# ATmega328P-StripBd.net
KiCad netlist of a schematic drawn in EAGLE
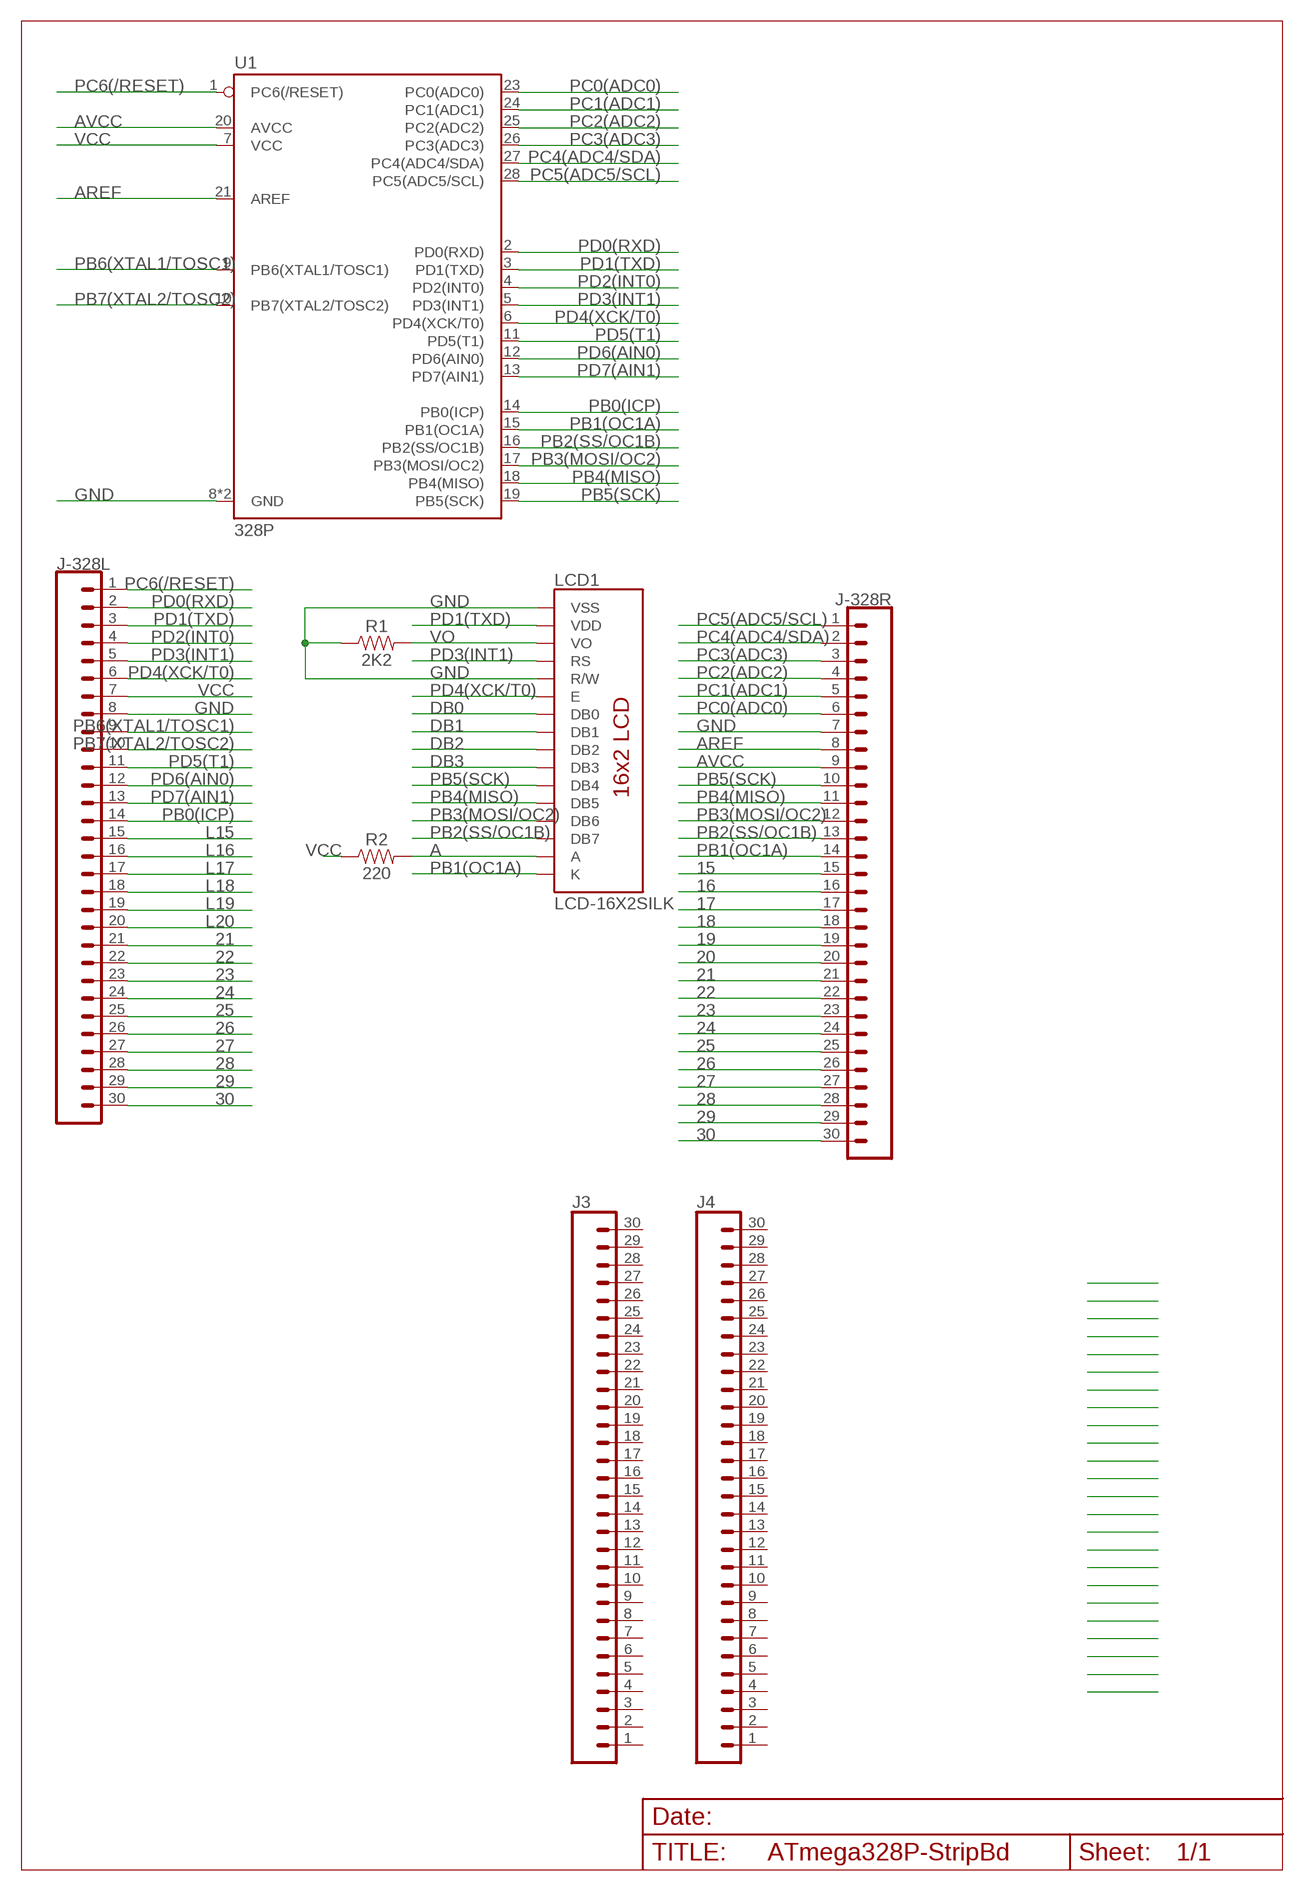
[diagram p0: schematic, sheet 1]

(export (version "E")
  (design (tool "Eeschema 10.0.6"))
  (components
    (comp (ref "J-328L")
      (value "CONN_30")
      (footprint "eagle-import:1X30")
      (libsource (lib "eagle-import") (part "CONN_30"))
    )
    (comp (ref "J-328R")
      (value "CONN_30")
      (footprint "eagle-import:1X30")
      (libsource (lib "eagle-import") (part "CONN_30"))
    )
    (comp (ref "J3")
      (value "CONN_30")
      (footprint "eagle-import:1X30")
      (libsource (lib "eagle-import") (part "CONN_30"))
    )
    (comp (ref "J4")
      (value "CONN_30")
      (footprint "eagle-import:1X30")
      (libsource (lib "eagle-import") (part "CONN_30"))
    )
    (comp (ref "LCD1")
      (value "LCD-16X2SILK")
      (footprint "eagle-import:LCD-16X2")
      (libsource (lib "eagle-import") (part "LCD-16X2SILK"))
    )
    (comp (ref "R1")
      (value "2K2")
      (footprint "eagle-import:AXIAL-0.3")
      (libsource (lib "eagle-import") (part "1KOHM-HORIZ-1/4W-5%"))
    )
    (comp (ref "R2")
      (value "220")
      (footprint "eagle-import:AXIAL-0.3")
      (libsource (lib "eagle-import") (part "1KOHM-HORIZ-1/4W-5%"))
    )
    (comp (ref "U1")
      (value "328P")
      (footprint "eagle-import:DIP28")
      (libsource (lib "eagle-import") (part "ATMEGA328P_PDIP"))
    )
  )
  (nets
    (net (code "1") (name "/15") (class "Default")
      (node (ref "J-328R") (pin "15") (pinfunction "15_15") (pintype "passive"))
    )
    (net (code "2") (name "/16") (class "Default")
      (node (ref "J-328R") (pin "16") (pinfunction "16_16") (pintype "passive"))
    )
    (net (code "3") (name "/17") (class "Default")
      (node (ref "J-328R") (pin "17") (pinfunction "17_17") (pintype "passive"))
    )
    (net (code "4") (name "/18") (class "Default")
      (node (ref "J-328R") (pin "18") (pinfunction "18_18") (pintype "passive"))
    )
    (net (code "5") (name "/19") (class "Default")
      (node (ref "J-328R") (pin "19") (pinfunction "19_19") (pintype "passive"))
    )
    (net (code "6") (name "/20") (class "Default")
      (node (ref "J-328R") (pin "20") (pinfunction "20_20") (pintype "passive"))
    )
    (net (code "7") (name "/21") (class "Default")
      (node (ref "J-328L") (pin "21") (pinfunction "21_21") (pintype "passive"))
      (node (ref "J-328R") (pin "21") (pinfunction "21_21") (pintype "passive"))
    )
    (net (code "8") (name "/22") (class "Default")
      (node (ref "J-328L") (pin "22") (pinfunction "22_22") (pintype "passive"))
      (node (ref "J-328R") (pin "22") (pinfunction "22_22") (pintype "passive"))
    )
    (net (code "9") (name "/23") (class "Default")
      (node (ref "J-328L") (pin "23") (pinfunction "23_23") (pintype "passive"))
      (node (ref "J-328R") (pin "23") (pinfunction "23_23") (pintype "passive"))
    )
    (net (code "10") (name "/24") (class "Default")
      (node (ref "J-328L") (pin "24") (pinfunction "24_24") (pintype "passive"))
      (node (ref "J-328R") (pin "24") (pinfunction "24_24") (pintype "passive"))
    )
    (net (code "11") (name "/25") (class "Default")
      (node (ref "J-328L") (pin "25") (pinfunction "25_25") (pintype "passive"))
      (node (ref "J-328R") (pin "25") (pinfunction "25_25") (pintype "passive"))
    )
    (net (code "12") (name "/26") (class "Default")
      (node (ref "J-328L") (pin "26") (pinfunction "26_26") (pintype "passive"))
      (node (ref "J-328R") (pin "26") (pinfunction "26_26") (pintype "passive"))
    )
    (net (code "13") (name "/27") (class "Default")
      (node (ref "J-328L") (pin "27") (pinfunction "27_27") (pintype "passive"))
      (node (ref "J-328R") (pin "27") (pinfunction "27_27") (pintype "passive"))
    )
    (net (code "14") (name "/28") (class "Default")
      (node (ref "J-328L") (pin "28") (pinfunction "28_28") (pintype "passive"))
      (node (ref "J-328R") (pin "28") (pinfunction "28_28") (pintype "passive"))
    )
    (net (code "15") (name "/29") (class "Default")
      (node (ref "J-328L") (pin "29") (pinfunction "29_29") (pintype "passive"))
      (node (ref "J-328R") (pin "29") (pinfunction "29_29") (pintype "passive"))
    )
    (net (code "16") (name "/30") (class "Default")
      (node (ref "J-328L") (pin "30") (pinfunction "30_30") (pintype "passive"))
      (node (ref "J-328R") (pin "30") (pinfunction "30_30") (pintype "passive"))
    )
    (net (code "17") (name "/A") (class "Default")
      (node (ref "LCD1") (pin "15") (pinfunction "A_15") (pintype "power_in"))
      (node (ref "R2") (pin "P$2") (pinfunction "2_P$2") (pintype "passive"))
    )
    (net (code "18") (name "/AREF") (class "Default")
      (node (ref "J-328R") (pin "8") (pinfunction "8_8") (pintype "passive"))
      (node (ref "U1") (pin "21") (pinfunction "AREF_21") (pintype "bidirectional"))
    )
    (net (code "19") (name "/AVCC") (class "Default")
      (node (ref "J-328R") (pin "9") (pinfunction "9_9") (pintype "passive"))
      (node (ref "U1") (pin "20") (pinfunction "AVCC_20") (pintype "bidirectional"))
    )
    (net (code "20") (name "/DB0") (class "Default")
      (node (ref "LCD1") (pin "7") (pinfunction "DB0_7") (pintype "bidirectional"))
    )
    (net (code "21") (name "/DB1") (class "Default")
      (node (ref "LCD1") (pin "8") (pinfunction "DB1_8") (pintype "bidirectional"))
    )
    (net (code "22") (name "/DB2") (class "Default")
      (node (ref "LCD1") (pin "9") (pinfunction "DB2_9") (pintype "bidirectional"))
    )
    (net (code "23") (name "/DB3") (class "Default")
      (node (ref "LCD1") (pin "10") (pinfunction "DB3_10") (pintype "bidirectional"))
    )
    (net (code "24") (name "/GND") (class "Default")
      (node (ref "J-328L") (pin "8") (pinfunction "8_8") (pintype "passive"))
      (node (ref "J-328R") (pin "7") (pinfunction "7_7") (pintype "passive"))
      (node (ref "LCD1") (pin "1") (pinfunction "VSS_1") (pintype "power_in"))
      (node (ref "LCD1") (pin "5") (pinfunction "R/W_5") (pintype "input"))
      (node (ref "R1") (pin "P$1") (pinfunction "1_P$1") (pintype "passive"))
      (node (ref "U1") (pin "22") (pinfunction "GND_22") (pintype "bidirectional"))
      (node (ref "U1") (pin "8") (pinfunction "GND_8") (pintype "bidirectional"))
    )
    (net (code "25") (name "/L15") (class "Default")
      (node (ref "J-328L") (pin "15") (pinfunction "15_15") (pintype "passive"))
    )
    (net (code "26") (name "/L16") (class "Default")
      (node (ref "J-328L") (pin "16") (pinfunction "16_16") (pintype "passive"))
    )
    (net (code "27") (name "/L17") (class "Default")
      (node (ref "J-328L") (pin "17") (pinfunction "17_17") (pintype "passive"))
    )
    (net (code "28") (name "/L18") (class "Default")
      (node (ref "J-328L") (pin "18") (pinfunction "18_18") (pintype "passive"))
    )
    (net (code "29") (name "/L19") (class "Default")
      (node (ref "J-328L") (pin "19") (pinfunction "19_19") (pintype "passive"))
    )
    (net (code "30") (name "/L20") (class "Default")
      (node (ref "J-328L") (pin "20") (pinfunction "20_20") (pintype "passive"))
    )
    (net (code "39") (name "/PB0(ICP)") (class "Default")
      (node (ref "J-328L") (pin "14") (pinfunction "14_14") (pintype "passive"))
      (node (ref "U1") (pin "14") (pinfunction "PB0(ICP)_14") (pintype "bidirectional"))
    )
    (net (code "40") (name "/PB1(OC1A)") (class "Default")
      (node (ref "J-328R") (pin "14") (pinfunction "14_14") (pintype "passive"))
      (node (ref "LCD1") (pin "16") (pinfunction "K_16") (pintype "power_in"))
      (node (ref "U1") (pin "15") (pinfunction "PB1(OC1A)_15") (pintype "bidirectional"))
    )
    (net (code "41") (name "/PB2(SS{slash}OC1B)") (class "Default")
      (node (ref "J-328R") (pin "13") (pinfunction "13_13") (pintype "passive"))
      (node (ref "LCD1") (pin "14") (pinfunction "DB7_14") (pintype "bidirectional"))
      (node (ref "U1") (pin "16") (pinfunction "PB2(SS/OC1B)_16") (pintype "bidirectional"))
    )
    (net (code "42") (name "/PB3(MOSI{slash}OC2)") (class "Default")
      (node (ref "J-328R") (pin "12") (pinfunction "12_12") (pintype "passive"))
      (node (ref "LCD1") (pin "13") (pinfunction "DB6_13") (pintype "bidirectional"))
      (node (ref "U1") (pin "17") (pinfunction "PB3(MOSI/OC2)_17") (pintype "bidirectional"))
    )
    (net (code "43") (name "/PB4(MISO)") (class "Default")
      (node (ref "J-328R") (pin "11") (pinfunction "11_11") (pintype "passive"))
      (node (ref "LCD1") (pin "12") (pinfunction "DB5_12") (pintype "bidirectional"))
      (node (ref "U1") (pin "18") (pinfunction "PB4(MISO)_18") (pintype "bidirectional"))
    )
    (net (code "44") (name "/PB5(SCK)") (class "Default")
      (node (ref "J-328R") (pin "10") (pinfunction "10_10") (pintype "passive"))
      (node (ref "LCD1") (pin "11") (pinfunction "DB4_11") (pintype "bidirectional"))
      (node (ref "U1") (pin "19") (pinfunction "PB5(SCK)_19") (pintype "bidirectional"))
    )
    (net (code "45") (name "/PB6(XTAL1{slash}TOSC1)") (class "Default")
      (node (ref "J-328L") (pin "9") (pinfunction "9_9") (pintype "passive"))
      (node (ref "U1") (pin "9") (pinfunction "PB6(XTAL1/TOSC1)_9") (pintype "bidirectional"))
    )
    (net (code "46") (name "/PB7(XTAL2{slash}TOSC2)") (class "Default")
      (node (ref "J-328L") (pin "10") (pinfunction "10_10") (pintype "passive"))
      (node (ref "U1") (pin "10") (pinfunction "PB7(XTAL2/TOSC2)_10") (pintype "bidirectional"))
    )
    (net (code "47") (name "/PC0(ADC0)") (class "Default")
      (node (ref "J-328R") (pin "6") (pinfunction "6_6") (pintype "passive"))
      (node (ref "U1") (pin "23") (pinfunction "PC0(ADC0)_23") (pintype "bidirectional"))
    )
    (net (code "48") (name "/PC1(ADC1)") (class "Default")
      (node (ref "J-328R") (pin "5") (pinfunction "5_5") (pintype "passive"))
      (node (ref "U1") (pin "24") (pinfunction "PC1(ADC1)_24") (pintype "bidirectional"))
    )
    (net (code "49") (name "/PC2(ADC2)") (class "Default")
      (node (ref "J-328R") (pin "4") (pinfunction "4_4") (pintype "passive"))
      (node (ref "U1") (pin "25") (pinfunction "PC2(ADC2)_25") (pintype "bidirectional"))
    )
    (net (code "50") (name "/PC3(ADC3)") (class "Default")
      (node (ref "J-328R") (pin "3") (pinfunction "3_3") (pintype "passive"))
      (node (ref "U1") (pin "26") (pinfunction "PC3(ADC3)_26") (pintype "bidirectional"))
    )
    (net (code "51") (name "/PC4(ADC4{slash}SDA)") (class "Default")
      (node (ref "J-328R") (pin "2") (pinfunction "2_2") (pintype "passive"))
      (node (ref "U1") (pin "27") (pinfunction "PC4(ADC4/SDA)_27") (pintype "bidirectional"))
    )
    (net (code "52") (name "/PC5(ADC5{slash}SCL)") (class "Default")
      (node (ref "J-328R") (pin "1") (pinfunction "1_1") (pintype "passive"))
      (node (ref "U1") (pin "28") (pinfunction "PC5(ADC5/SCL)_28") (pintype "bidirectional"))
    )
    (net (code "53") (name "/PC6({slash}RESET)") (class "Default")
      (node (ref "J-328L") (pin "1") (pinfunction "1_1") (pintype "passive"))
      (node (ref "U1") (pin "1") (pinfunction "PC6(/RESET)_1") (pintype "bidirectional"))
    )
    (net (code "54") (name "/PD0(RXD)") (class "Default")
      (node (ref "J-328L") (pin "2") (pinfunction "2_2") (pintype "passive"))
      (node (ref "U1") (pin "2") (pinfunction "PD0(RXD)_2") (pintype "bidirectional"))
    )
    (net (code "55") (name "/PD1(TXD)") (class "Default")
      (node (ref "J-328L") (pin "3") (pinfunction "3_3") (pintype "passive"))
      (node (ref "LCD1") (pin "2") (pinfunction "VDD_2") (pintype "power_in"))
      (node (ref "U1") (pin "3") (pinfunction "PD1(TXD)_3") (pintype "bidirectional"))
    )
    (net (code "56") (name "/PD2(INT0)") (class "Default")
      (node (ref "J-328L") (pin "4") (pinfunction "4_4") (pintype "passive"))
      (node (ref "U1") (pin "4") (pinfunction "PD2(INT0)_4") (pintype "bidirectional"))
    )
    (net (code "57") (name "/PD3(INT1)") (class "Default")
      (node (ref "J-328L") (pin "5") (pinfunction "5_5") (pintype "passive"))
      (node (ref "LCD1") (pin "4") (pinfunction "RS_4") (pintype "input"))
      (node (ref "U1") (pin "5") (pinfunction "PD3(INT1)_5") (pintype "bidirectional"))
    )
    (net (code "58") (name "/PD4(XCK{slash}T0)") (class "Default")
      (node (ref "J-328L") (pin "6") (pinfunction "6_6") (pintype "passive"))
      (node (ref "LCD1") (pin "6") (pinfunction "E_6") (pintype "input"))
      (node (ref "U1") (pin "6") (pinfunction "PD4(XCK/T0)_6") (pintype "bidirectional"))
    )
    (net (code "59") (name "/PD5(T1)") (class "Default")
      (node (ref "J-328L") (pin "11") (pinfunction "11_11") (pintype "passive"))
      (node (ref "U1") (pin "11") (pinfunction "PD5(T1)_11") (pintype "bidirectional"))
    )
    (net (code "60") (name "/PD6(AIN0)") (class "Default")
      (node (ref "J-328L") (pin "12") (pinfunction "12_12") (pintype "passive"))
      (node (ref "U1") (pin "12") (pinfunction "PD6(AIN0)_12") (pintype "bidirectional"))
    )
    (net (code "61") (name "/PD7(AIN1)") (class "Default")
      (node (ref "J-328L") (pin "13") (pinfunction "13_13") (pintype "passive"))
      (node (ref "U1") (pin "13") (pinfunction "PD7(AIN1)_13") (pintype "bidirectional"))
    )
    (net (code "62") (name "/VCC") (class "Default")
      (node (ref "J-328L") (pin "7") (pinfunction "7_7") (pintype "passive"))
      (node (ref "R2") (pin "P$1") (pinfunction "1_P$1") (pintype "passive"))
      (node (ref "U1") (pin "7") (pinfunction "VCC_7") (pintype "bidirectional"))
    )
    (net (code "63") (name "/VO") (class "Default")
      (node (ref "LCD1") (pin "3") (pinfunction "VO_3") (pintype "bidirectional"))
      (node (ref "R1") (pin "P$2") (pinfunction "2_P$2") (pintype "passive"))
    )
    (net (code "64") (name "unconnected-(J3-Pad1)") (class "Default")
      (node (ref "J3") (pin "1") (pinfunction "1_1") (pintype "passive"))
    )
    (net (code "65") (name "unconnected-(J3-Pad2)") (class "Default")
      (node (ref "J3") (pin "2") (pinfunction "2_2") (pintype "passive"))
    )
    (net (code "66") (name "unconnected-(J3-Pad3)") (class "Default")
      (node (ref "J3") (pin "3") (pinfunction "3_3") (pintype "passive"))
    )
    (net (code "67") (name "unconnected-(J3-Pad4)") (class "Default")
      (node (ref "J3") (pin "4") (pinfunction "4_4") (pintype "passive"))
    )
    (net (code "68") (name "unconnected-(J3-Pad5)") (class "Default")
      (node (ref "J3") (pin "5") (pinfunction "5_5") (pintype "passive"))
    )
    (net (code "69") (name "unconnected-(J3-Pad6)") (class "Default")
      (node (ref "J3") (pin "6") (pinfunction "6_6") (pintype "passive"))
    )
    (net (code "70") (name "unconnected-(J3-Pad7)") (class "Default")
      (node (ref "J3") (pin "7") (pinfunction "7_7") (pintype "passive"))
    )
    (net (code "71") (name "unconnected-(J3-Pad8)") (class "Default")
      (node (ref "J3") (pin "8") (pinfunction "8_8") (pintype "passive"))
    )
    (net (code "72") (name "unconnected-(J3-Pad9)") (class "Default")
      (node (ref "J3") (pin "9") (pinfunction "9_9") (pintype "passive"))
    )
    (net (code "73") (name "unconnected-(J3-Pad10)") (class "Default")
      (node (ref "J3") (pin "10") (pinfunction "10_10") (pintype "passive"))
    )
    (net (code "74") (name "unconnected-(J3-Pad11)") (class "Default")
      (node (ref "J3") (pin "11") (pinfunction "11_11") (pintype "passive"))
    )
    (net (code "75") (name "unconnected-(J3-Pad12)") (class "Default")
      (node (ref "J3") (pin "12") (pinfunction "12_12") (pintype "passive"))
    )
    (net (code "76") (name "unconnected-(J3-Pad13)") (class "Default")
      (node (ref "J3") (pin "13") (pinfunction "13_13") (pintype "passive"))
    )
    (net (code "77") (name "unconnected-(J3-Pad14)") (class "Default")
      (node (ref "J3") (pin "14") (pinfunction "14_14") (pintype "passive"))
    )
    (net (code "78") (name "unconnected-(J3-Pad15)") (class "Default")
      (node (ref "J3") (pin "15") (pinfunction "15_15") (pintype "passive"))
    )
    (net (code "79") (name "unconnected-(J3-Pad16)") (class "Default")
      (node (ref "J3") (pin "16") (pinfunction "16_16") (pintype "passive"))
    )
    (net (code "80") (name "unconnected-(J3-Pad17)") (class "Default")
      (node (ref "J3") (pin "17") (pinfunction "17_17") (pintype "passive"))
    )
    (net (code "81") (name "unconnected-(J3-Pad18)") (class "Default")
      (node (ref "J3") (pin "18") (pinfunction "18_18") (pintype "passive"))
    )
    (net (code "82") (name "unconnected-(J3-Pad19)") (class "Default")
      (node (ref "J3") (pin "19") (pinfunction "19_19") (pintype "passive"))
    )
    (net (code "83") (name "unconnected-(J3-Pad20)") (class "Default")
      (node (ref "J3") (pin "20") (pinfunction "20_20") (pintype "passive"))
    )
    (net (code "84") (name "unconnected-(J3-Pad21)") (class "Default")
      (node (ref "J3") (pin "21") (pinfunction "21_21") (pintype "passive"))
    )
    (net (code "85") (name "unconnected-(J3-Pad22)") (class "Default")
      (node (ref "J3") (pin "22") (pinfunction "22_22") (pintype "passive"))
    )
    (net (code "86") (name "unconnected-(J3-Pad23)") (class "Default")
      (node (ref "J3") (pin "23") (pinfunction "23_23") (pintype "passive"))
    )
    (net (code "87") (name "unconnected-(J3-Pad24)") (class "Default")
      (node (ref "J3") (pin "24") (pinfunction "24_24") (pintype "passive"))
    )
    (net (code "88") (name "unconnected-(J3-Pad25)") (class "Default")
      (node (ref "J3") (pin "25") (pinfunction "25_25") (pintype "passive"))
    )
    (net (code "89") (name "unconnected-(J3-Pad26)") (class "Default")
      (node (ref "J3") (pin "26") (pinfunction "26_26") (pintype "passive"))
    )
    (net (code "90") (name "unconnected-(J3-Pad27)") (class "Default")
      (node (ref "J3") (pin "27") (pinfunction "27_27") (pintype "passive"))
    )
    (net (code "91") (name "unconnected-(J3-Pad28)") (class "Default")
      (node (ref "J3") (pin "28") (pinfunction "28_28") (pintype "passive"))
    )
    (net (code "92") (name "unconnected-(J3-Pad29)") (class "Default")
      (node (ref "J3") (pin "29") (pinfunction "29_29") (pintype "passive"))
    )
    (net (code "93") (name "unconnected-(J3-Pad30)") (class "Default")
      (node (ref "J3") (pin "30") (pinfunction "30_30") (pintype "passive"))
    )
    (net (code "94") (name "unconnected-(J4-Pad1)") (class "Default")
      (node (ref "J4") (pin "1") (pinfunction "1_1") (pintype "passive"))
    )
    (net (code "95") (name "unconnected-(J4-Pad2)") (class "Default")
      (node (ref "J4") (pin "2") (pinfunction "2_2") (pintype "passive"))
    )
    (net (code "96") (name "unconnected-(J4-Pad3)") (class "Default")
      (node (ref "J4") (pin "3") (pinfunction "3_3") (pintype "passive"))
    )
    (net (code "97") (name "unconnected-(J4-Pad4)") (class "Default")
      (node (ref "J4") (pin "4") (pinfunction "4_4") (pintype "passive"))
    )
    (net (code "98") (name "unconnected-(J4-Pad5)") (class "Default")
      (node (ref "J4") (pin "5") (pinfunction "5_5") (pintype "passive"))
    )
    (net (code "99") (name "unconnected-(J4-Pad6)") (class "Default")
      (node (ref "J4") (pin "6") (pinfunction "6_6") (pintype "passive"))
    )
    (net (code "100") (name "unconnected-(J4-Pad7)") (class "Default")
      (node (ref "J4") (pin "7") (pinfunction "7_7") (pintype "passive"))
    )
    (net (code "101") (name "unconnected-(J4-Pad8)") (class "Default")
      (node (ref "J4") (pin "8") (pinfunction "8_8") (pintype "passive"))
    )
    (net (code "102") (name "unconnected-(J4-Pad9)") (class "Default")
      (node (ref "J4") (pin "9") (pinfunction "9_9") (pintype "passive"))
    )
    (net (code "103") (name "unconnected-(J4-Pad10)") (class "Default")
      (node (ref "J4") (pin "10") (pinfunction "10_10") (pintype "passive"))
    )
    (net (code "104") (name "unconnected-(J4-Pad11)") (class "Default")
      (node (ref "J4") (pin "11") (pinfunction "11_11") (pintype "passive"))
    )
    (net (code "105") (name "unconnected-(J4-Pad12)") (class "Default")
      (node (ref "J4") (pin "12") (pinfunction "12_12") (pintype "passive"))
    )
    (net (code "106") (name "unconnected-(J4-Pad13)") (class "Default")
      (node (ref "J4") (pin "13") (pinfunction "13_13") (pintype "passive"))
    )
    (net (code "107") (name "unconnected-(J4-Pad14)") (class "Default")
      (node (ref "J4") (pin "14") (pinfunction "14_14") (pintype "passive"))
    )
    (net (code "108") (name "unconnected-(J4-Pad15)") (class "Default")
      (node (ref "J4") (pin "15") (pinfunction "15_15") (pintype "passive"))
    )
    (net (code "109") (name "unconnected-(J4-Pad16)") (class "Default")
      (node (ref "J4") (pin "16") (pinfunction "16_16") (pintype "passive"))
    )
    (net (code "110") (name "unconnected-(J4-Pad17)") (class "Default")
      (node (ref "J4") (pin "17") (pinfunction "17_17") (pintype "passive"))
    )
    (net (code "111") (name "unconnected-(J4-Pad18)") (class "Default")
      (node (ref "J4") (pin "18") (pinfunction "18_18") (pintype "passive"))
    )
    (net (code "112") (name "unconnected-(J4-Pad19)") (class "Default")
      (node (ref "J4") (pin "19") (pinfunction "19_19") (pintype "passive"))
    )
    (net (code "113") (name "unconnected-(J4-Pad20)") (class "Default")
      (node (ref "J4") (pin "20") (pinfunction "20_20") (pintype "passive"))
    )
    (net (code "114") (name "unconnected-(J4-Pad21)") (class "Default")
      (node (ref "J4") (pin "21") (pinfunction "21_21") (pintype "passive"))
    )
    (net (code "115") (name "unconnected-(J4-Pad22)") (class "Default")
      (node (ref "J4") (pin "22") (pinfunction "22_22") (pintype "passive"))
    )
    (net (code "116") (name "unconnected-(J4-Pad23)") (class "Default")
      (node (ref "J4") (pin "23") (pinfunction "23_23") (pintype "passive"))
    )
    (net (code "117") (name "unconnected-(J4-Pad24)") (class "Default")
      (node (ref "J4") (pin "24") (pinfunction "24_24") (pintype "passive"))
    )
    (net (code "118") (name "unconnected-(J4-Pad25)") (class "Default")
      (node (ref "J4") (pin "25") (pinfunction "25_25") (pintype "passive"))
    )
    (net (code "119") (name "unconnected-(J4-Pad26)") (class "Default")
      (node (ref "J4") (pin "26") (pinfunction "26_26") (pintype "passive"))
    )
    (net (code "120") (name "unconnected-(J4-Pad27)") (class "Default")
      (node (ref "J4") (pin "27") (pinfunction "27_27") (pintype "passive"))
    )
    (net (code "121") (name "unconnected-(J4-Pad28)") (class "Default")
      (node (ref "J4") (pin "28") (pinfunction "28_28") (pintype "passive"))
    )
    (net (code "122") (name "unconnected-(J4-Pad29)") (class "Default")
      (node (ref "J4") (pin "29") (pinfunction "29_29") (pintype "passive"))
    )
    (net (code "123") (name "unconnected-(J4-Pad30)") (class "Default")
      (node (ref "J4") (pin "30") (pinfunction "30_30") (pintype "passive"))
    )
  )
)
